# rear_wheel_encoder.net
KiCad netlist of a schematic drawn in EAGLE
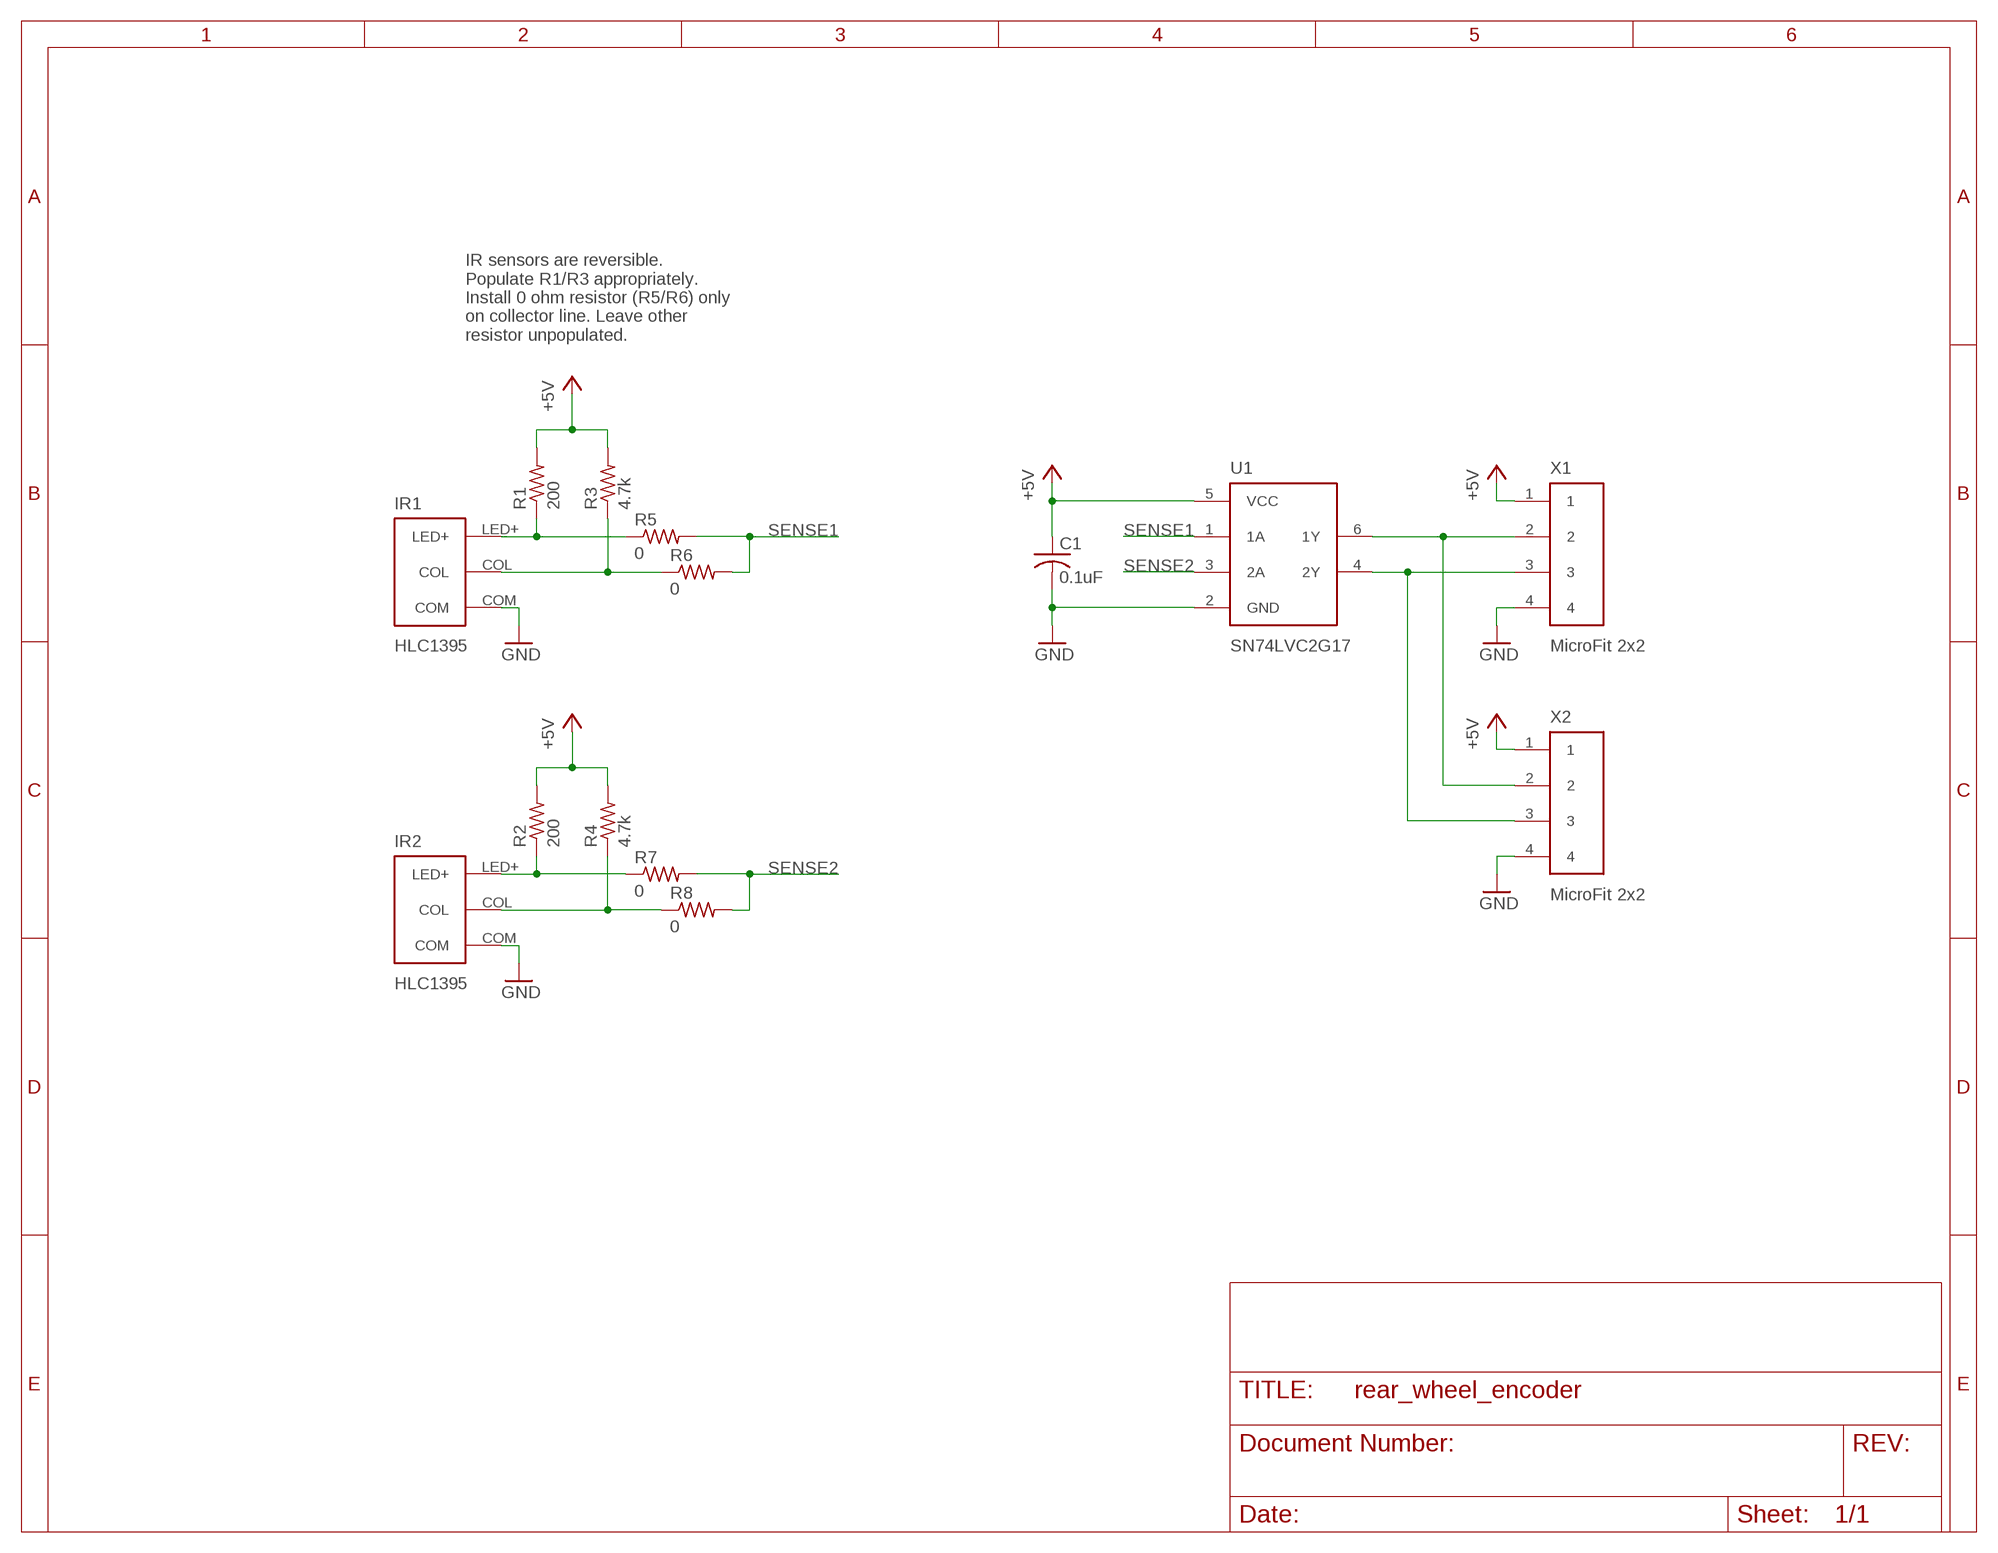
[diagram p0: schematic, sheet 1]

(export (version "E")
  (design (tool "Eeschema 10.0.6"))
  (components
    (comp (ref "C1")
      (value "0.1uF")
      (footprint "eagle-import:C0603")
      (libsource (lib "eagle-import") (part "C-USC0603"))
    )
    (comp (ref "IR1")
      (value "HLC1395")
      (footprint "eagle-import:HLC1395")
      (libsource (lib "eagle-import") (part "HLC1395"))
    )
    (comp (ref "IR2")
      (value "HLC1395")
      (footprint "eagle-import:HLC1395")
      (libsource (lib "eagle-import") (part "HLC1395"))
    )
    (comp (ref "R1")
      (value "200")
      (footprint "eagle-import:R0603")
      (libsource (lib "eagle-import") (part "R-US_R0603"))
    )
    (comp (ref "R2")
      (value "200")
      (footprint "eagle-import:R0603")
      (libsource (lib "eagle-import") (part "R-US_R0603"))
    )
    (comp (ref "R3")
      (value "4.7k")
      (footprint "eagle-import:R0603")
      (libsource (lib "eagle-import") (part "R-US_R0603"))
    )
    (comp (ref "R4")
      (value "4.7k")
      (footprint "eagle-import:R0603")
      (libsource (lib "eagle-import") (part "R-US_R0603"))
    )
    (comp (ref "R5")
      (value "0")
      (footprint "eagle-import:R0603")
      (libsource (lib "eagle-import") (part "R-US_R0603"))
    )
    (comp (ref "R6")
      (value "0")
      (footprint "eagle-import:R0603")
      (libsource (lib "eagle-import") (part "R-US_R0603"))
    )
    (comp (ref "R7")
      (value "0")
      (footprint "eagle-import:R0603")
      (libsource (lib "eagle-import") (part "R-US_R0603"))
    )
    (comp (ref "R8")
      (value "0")
      (footprint "eagle-import:R0603")
      (libsource (lib "eagle-import") (part "R-US_R0603"))
    )
    (comp (ref "U1")
      (value "SN74LVC2G17DBVR")
      (footprint "eagle-import:SOT-23-6")
      (libsource (lib "eagle-import") (part "SN74LVC2G17DBVR"))
    )
    (comp (ref "X1")
      (value "MICROFIT-2X2-SMD")
      (footprint "eagle-import:MICROFIT-2X2-0430450411")
      (libsource (lib "eagle-import") (part "MICROFIT-2X2-SMD"))
    )
    (comp (ref "X2")
      (value "MICROFIT-2X2-SMD")
      (footprint "eagle-import:MICROFIT-2X2-0430450411")
      (libsource (lib "eagle-import") (part "MICROFIT-2X2-SMD"))
    )
  )
  (nets
    (net (code "1") (name "+5V") (class "Default")
      (node (ref "C1") (pin "1") (pinfunction "1_1") (pintype "passive"))
      (node (ref "R1") (pin "2") (pinfunction "2_2") (pintype "passive"))
      (node (ref "R2") (pin "2") (pinfunction "2_2") (pintype "passive"))
      (node (ref "R3") (pin "2") (pinfunction "2_2") (pintype "passive"))
      (node (ref "R4") (pin "2") (pinfunction "2_2") (pintype "passive"))
      (node (ref "U1") (pin "5") (pinfunction "VCC_5") (pintype "power_in"))
      (node (ref "X1") (pin "1") (pinfunction "1_1") (pintype "bidirectional"))
      (node (ref "X2") (pin "1") (pinfunction "1_1") (pintype "bidirectional"))
    )
    (net (code "2") (name "/SENSE1") (class "Default")
      (node (ref "R5") (pin "2") (pinfunction "2_2") (pintype "passive"))
      (node (ref "R6") (pin "2") (pinfunction "2_2") (pintype "passive"))
      (node (ref "U1") (pin "1") (pinfunction "1A_1") (pintype "input"))
    )
    (net (code "3") (name "/SENSE2") (class "Default")
      (node (ref "R7") (pin "2") (pinfunction "2_2") (pintype "passive"))
      (node (ref "R8") (pin "2") (pinfunction "2_2") (pintype "passive"))
      (node (ref "U1") (pin "3") (pinfunction "2A_3") (pintype "input"))
    )
    (net (code "4") (name "GND") (class "Default")
      (node (ref "C1") (pin "2") (pinfunction "2_2") (pintype "passive"))
      (node (ref "IR1") (pin "COM") (pinfunction "COM_COM") (pintype "power_in"))
      (node (ref "IR2") (pin "COM") (pinfunction "COM_COM") (pintype "power_in"))
      (node (ref "U1") (pin "2") (pinfunction "GND_2") (pintype "power_in"))
      (node (ref "X1") (pin "4") (pinfunction "4_4") (pintype "bidirectional"))
      (node (ref "X2") (pin "4") (pinfunction "4_4") (pintype "bidirectional"))
    )
    (net (code "5") (name "Net-(IR1-PadCOL)") (class "Default")
      (node (ref "IR1") (pin "COL") (pinfunction "COL_COL") (pintype "input"))
      (node (ref "R3") (pin "1") (pinfunction "1_1") (pintype "passive"))
      (node (ref "R6") (pin "1") (pinfunction "1_1") (pintype "passive"))
    )
    (net (code "6") (name "Net-(IR1-PadLED+)") (class "Default")
      (node (ref "IR1") (pin "LED+") (pinfunction "LED+_LED+") (pintype "input"))
      (node (ref "R1") (pin "1") (pinfunction "1_1") (pintype "passive"))
      (node (ref "R5") (pin "1") (pinfunction "1_1") (pintype "passive"))
    )
    (net (code "7") (name "Net-(IR2-PadCOL)") (class "Default")
      (node (ref "IR2") (pin "COL") (pinfunction "COL_COL") (pintype "input"))
      (node (ref "R4") (pin "1") (pinfunction "1_1") (pintype "passive"))
      (node (ref "R8") (pin "1") (pinfunction "1_1") (pintype "passive"))
    )
    (net (code "8") (name "Net-(IR2-PadLED+)") (class "Default")
      (node (ref "IR2") (pin "LED+") (pinfunction "LED+_LED+") (pintype "input"))
      (node (ref "R2") (pin "1") (pinfunction "1_1") (pintype "passive"))
      (node (ref "R7") (pin "1") (pinfunction "1_1") (pintype "passive"))
    )
    (net (code "9") (name "Net-(U1-1Y)") (class "Default")
      (node (ref "U1") (pin "6") (pinfunction "1Y_6") (pintype "output"))
      (node (ref "X1") (pin "2") (pinfunction "2_2") (pintype "bidirectional"))
      (node (ref "X2") (pin "2") (pinfunction "2_2") (pintype "bidirectional"))
    )
    (net (code "10") (name "Net-(U1-2Y)") (class "Default")
      (node (ref "U1") (pin "4") (pinfunction "2Y_4") (pintype "output"))
      (node (ref "X1") (pin "3") (pinfunction "3_3") (pintype "bidirectional"))
      (node (ref "X2") (pin "3") (pinfunction "3_3") (pintype "bidirectional"))
    )
  )
)
